# Ethernet_Adapter.net
KiCad netlist of a schematic drawn in EAGLE
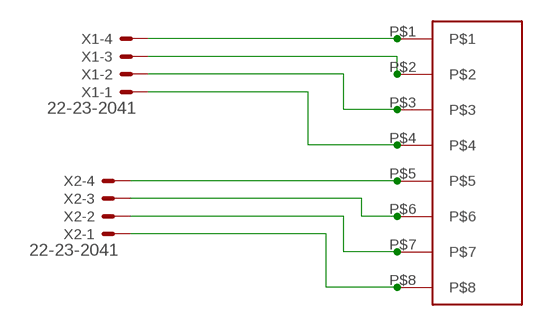
[diagram p0: schematic, sheet 1]

(export (version "E")
  (design (tool "Eeschema 10.0.6"))
  (components
    (comp (ref "U$1")
      (value "ETHERNETPORT")
      (footprint "eagle-import:ETHERNETPORT")
      (libsource (lib "eagle-import") (part "ETHERNETPORT"))
    )
    (comp (ref "X1")
      (value "22-23-2041")
      (footprint "eagle-import:22-23-2041")
      (fields (field (name "MF") "MOLEX"))
      (libsource (lib "eagle-import") (part "22-23-2041"))
    )
    (comp (ref "X2")
      (value "22-23-2041")
      (footprint "eagle-import:22-23-2041")
      (fields (field (name "MF") "MOLEX"))
      (libsource (lib "eagle-import") (part "22-23-2041"))
    )
  )
  (nets
    (net (code "1") (name "Net-(X1A-S)") (class "Default")
      (node (ref "U$1") (pin "P$4") (pinfunction "P$4_P$4") (pintype "bidirectional"))
      (node (ref "X1") (pin "1") (pinfunction "S_1") (pintype "passive"))
    )
    (net (code "2") (name "Net-(X1B-S)") (class "Default")
      (node (ref "U$1") (pin "P$3") (pinfunction "P$3_P$3") (pintype "bidirectional"))
      (node (ref "X1") (pin "2") (pinfunction "S_2") (pintype "passive"))
    )
    (net (code "3") (name "Net-(X1C-S)") (class "Default")
      (node (ref "U$1") (pin "P$2") (pinfunction "P$2_P$2") (pintype "bidirectional"))
      (node (ref "X1") (pin "3") (pinfunction "S_3") (pintype "passive"))
    )
    (net (code "4") (name "Net-(X1D-S)") (class "Default")
      (node (ref "U$1") (pin "P$1") (pinfunction "P$1_P$1") (pintype "bidirectional"))
      (node (ref "X1") (pin "4") (pinfunction "S_4") (pintype "passive"))
    )
    (net (code "5") (name "Net-(X2A-S)") (class "Default")
      (node (ref "U$1") (pin "P$8") (pinfunction "P$8_P$8") (pintype "bidirectional"))
      (node (ref "X2") (pin "1") (pinfunction "S_1") (pintype "passive"))
    )
    (net (code "6") (name "Net-(X2B-S)") (class "Default")
      (node (ref "U$1") (pin "P$7") (pinfunction "P$7_P$7") (pintype "bidirectional"))
      (node (ref "X2") (pin "2") (pinfunction "S_2") (pintype "passive"))
    )
    (net (code "7") (name "Net-(X2C-S)") (class "Default")
      (node (ref "U$1") (pin "P$6") (pinfunction "P$6_P$6") (pintype "bidirectional"))
      (node (ref "X2") (pin "3") (pinfunction "S_3") (pintype "passive"))
    )
    (net (code "8") (name "Net-(X2D-S)") (class "Default")
      (node (ref "U$1") (pin "P$5") (pinfunction "P$5_P$5") (pintype "bidirectional"))
      (node (ref "X2") (pin "4") (pinfunction "S_4") (pintype "passive"))
    )
  )
)
